# OSPLC2_2_CPU2.net
KiCad netlist of a schematic drawn in Altium Designer
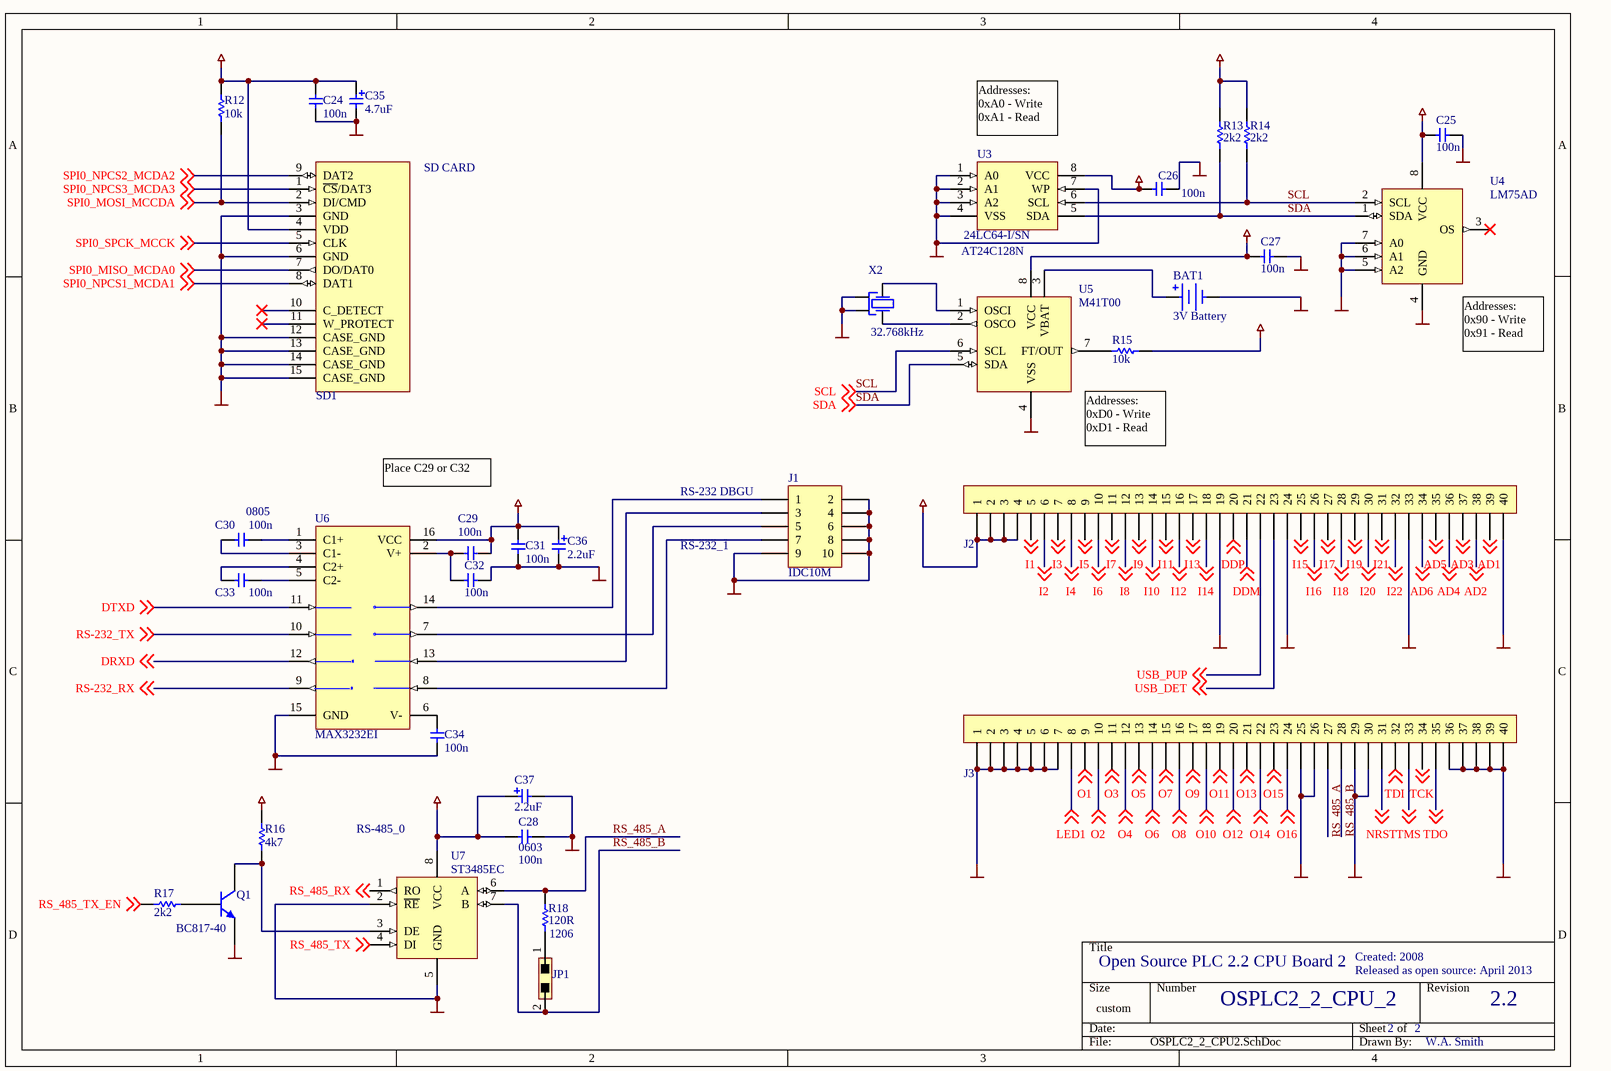
[diagram p0: OSPLC2_2_CPU2.SchDoc]

(export (version "E")
  (design (tool "Eeschema 10.0.6"))
  (components
    (comp (ref "BAT1")
      (value "3V Battery")
      (footprint "BATTERY_22MM")
      (description "3 Volt Lithium Button Battery")
      (libsource (lib "ARM_projects") (part "BATTERY_22MM"))
    )
    (comp (ref "C24")
      (value "0603")
      (footprint "0603")
      (description "0603 footprint non-polorised capacitor")
      (fields (field (name "ALTIUM_VALUE") "100n"))
      (libsource (lib "Integrated Comp_lib") (part "CAP_0603"))
    )
    (comp (ref "C25")
      (value "0603")
      (footprint "0603")
      (description "0603 footprint non-polorised capacitor")
      (fields (field (name "ALTIUM_VALUE") "100n"))
      (libsource (lib "Integrated Comp_lib") (part "CAP_0603"))
    )
    (comp (ref "C26")
      (value "0603")
      (footprint "0603")
      (description "0603 footprint non-polorised capacitor")
      (fields (field (name "ALTIUM_VALUE") "100n"))
      (libsource (lib "Integrated Comp_lib") (part "CAP_0603"))
    )
    (comp (ref "C27")
      (value "0603")
      (footprint "0603")
      (description "0603 footprint non-polorised capacitor")
      (fields (field (name "ALTIUM_VALUE") "100n"))
      (libsource (lib "Integrated Comp_lib") (part "CAP_0603"))
    )
    (comp (ref "C28")
      (value "0603")
      (footprint "0603")
      (description "0603 footprint non-polorised capacitor")
      (fields (field (name "ALTIUM_VALUE") "100n"))
      (libsource (lib "Integrated Comp_lib") (part "CAP_0603"))
    )
    (comp (ref "C29")
      (value "0805")
      (footprint "0805")
      (description "0805 footprint non-polarised capacitor")
      (fields (field (name "ALTIUM_VALUE") "100n"))
      (libsource (lib "Integrated Comp_lib") (part "CAP_0805"))
    )
    (comp (ref "C30")
      (value "0805")
      (footprint "0805")
      (description "0805 footprint non-polarised capacitor")
      (fields (field (name "ALTIUM_VALUE") "100n"))
      (libsource (lib "Integrated Comp_lib") (part "CAP_0805"))
    )
    (comp (ref "C31")
      (value "0805")
      (footprint "0805")
      (description "0805 footprint non-polarised capacitor")
      (fields (field (name "ALTIUM_VALUE") "100n"))
      (libsource (lib "Integrated Comp_lib") (part "CAP_0805"))
    )
    (comp (ref "C32")
      (value "0805")
      (footprint "0805")
      (description "0805 footprint non-polarised capacitor")
      (fields (field (name "ALTIUM_VALUE") "100n"))
      (libsource (lib "Integrated Comp_lib") (part "CAP_0805"))
    )
    (comp (ref "C33")
      (value "0805")
      (footprint "0805")
      (description "0805 footprint non-polarised capacitor")
      (fields (field (name "ALTIUM_VALUE") "100n"))
      (libsource (lib "Integrated Comp_lib") (part "CAP_0805"))
    )
    (comp (ref "C34")
      (value "0805")
      (footprint "0805")
      (description "0805 footprint non-polarised capacitor")
      (fields (field (name "ALTIUM_VALUE") "100n"))
      (libsource (lib "Integrated Comp_lib") (part "CAP_0805"))
    )
    (comp (ref "C35")
      (value "Tant_A")
      (footprint "CAP_TANT_A")
      (description "Tantalum Capacitor, A Package")
      (fields (field (name "ALTIUM_VALUE") "4.7uF"))
      (libsource (lib "Integrated Comp_lib") (part "CAP_TANT_A"))
    )
    (comp (ref "C36")
      (value "Tant_A")
      (footprint "CAP_TANT_A")
      (description "Tantalum Capacitor, A Package")
      (fields (field (name "ALTIUM_VALUE") "2.2uF"))
      (libsource (lib "Integrated Comp_lib") (part "CAP_TANT_A"))
    )
    (comp (ref "C37")
      (value "Tant_A")
      (footprint "CAP_TANT_A")
      (description "Tantalum Capacitor, A Package")
      (fields (field (name "ALTIUM_VALUE") "2.2uF"))
      (libsource (lib "Integrated Comp_lib") (part "CAP_TANT_A"))
    )
    (comp (ref "J1")
      (value "IDC10M")
      (footprint "IDC_10M_BOX")
      (description "10 pin IDC male connector, vertical, box")
      (libsource (lib "Integrated Comp_lib") (part "IDC_10M"))
    )
    (comp (ref "J2")
      (value "HEADER 1 x 40")
      (footprint "HEADER_1_40")
      (description "2.54mm header, 1 by 40")
      (libsource (lib "ARM_projects") (part "HEADER_1_40"))
    )
    (comp (ref "J3")
      (value "HEADER 1 x 40")
      (footprint "HEADER_1_40")
      (description "2.54mm header, 1 by 40")
      (libsource (lib "ARM_projects") (part "HEADER_1_40"))
    )
    (comp (ref "JP1")
      (value "JUMPER2")
      (footprint "JUMPER2_254")
      (description "2 Pin Jumper, 2.54mm")
      (libsource (lib "ARM_projects") (part "JUMPER2"))
    )
    (comp (ref "Q1")
      (value "BC817-40")
      (footprint "SO-G3/Y1")
      (description "NPN General Purpose Amplifier")
      (fields
        (field (name "MANUFACTURER") "Fairchild Semiconductor")
        (field (name "PUBLISHER") "Altium Limited")
      )
      (libsource (lib "FSC Discrete BJT") (part "BC817-40"))
    )
    (comp (ref "R12")
      (value "0805")
      (footprint "0805")
      (description "0805 footprint resistor")
      (fields (field (name "ALTIUM_VALUE") "10k"))
      (libsource (lib "Integrated Comp_lib") (part "RES_0805"))
    )
    (comp (ref "R13")
      (value "0805")
      (footprint "0805")
      (description "0805 footprint resistor")
      (fields (field (name "ALTIUM_VALUE") "2k2"))
      (libsource (lib "Integrated Comp_lib") (part "RES_0805"))
    )
    (comp (ref "R14")
      (value "0805")
      (footprint "0805")
      (description "0805 footprint resistor")
      (fields (field (name "ALTIUM_VALUE") "2k2"))
      (libsource (lib "Integrated Comp_lib") (part "RES_0805"))
    )
    (comp (ref "R15")
      (value "0805")
      (footprint "0805")
      (description "0805 footprint resistor")
      (fields (field (name "ALTIUM_VALUE") "10k"))
      (libsource (lib "Integrated Comp_lib") (part "RES_0805"))
    )
    (comp (ref "R16")
      (value "0805")
      (footprint "0805")
      (description "0805 footprint resistor")
      (fields (field (name "ALTIUM_VALUE") "4k7"))
      (libsource (lib "Integrated Comp_lib") (part "RES_0805"))
    )
    (comp (ref "R17")
      (value "0805")
      (footprint "0805")
      (description "0805 footprint resistor")
      (fields (field (name "ALTIUM_VALUE") "2k2"))
      (libsource (lib "Integrated Comp_lib") (part "RES_0805"))
    )
    (comp (ref "R18")
      (value "1206")
      (footprint "1206")
      (description "1206 footprint resistor")
      (fields (field (name "ALTIUM_VALUE") "120R"))
      (libsource (lib "Integrated Comp_lib") (part "RES_1206"))
    )
    (comp (ref "SD1")
      (value "SD Card Connector")
      (footprint "SD_CARD_GS09003P")
      (description "Secure Digital Card Connector, Amphenol, GSD09003P")
      (libsource (lib "ARM_projects") (part "SD_CARD_GSD09003P"))
    )
    (comp (ref "U3")
      (value "24LC64-I/SN")
      (footprint "SO-G8/Z7.4")
      (description "Microchip 64k bit I2C bus serial EEPROM")
      (fields (field (name "ALTIUM_VALUE") "AT24C128N"))
      (libsource (lib "Integrated Comp_lib") (part "24LC64-I/SN"))
    )
    (comp (ref "U4")
      (value "LM75AD")
      (footprint "SO-G8/X.6")
      (description "Phillips Digital temperature sensor and thermal Watchdog")
      (libsource (lib "Integrated Comp_lib") (part "LM75AD"))
    )
    (comp (ref "U5")
      (value "M41T00")
      (footprint "SO-G8/X.6")
      (description "ST Serial Access Timekeeper")
      (libsource (lib "Integrated Comp_lib") (part "M41T00"))
    )
    (comp (ref "U6")
      (value "MAX3232EI")
      (footprint "SO-G16")
      (description "3.0V TO 5.5V, Low-Power, up to 1Mbps, True RS-232 Transceiver Using Four 0.1µF External Capacitor")
      (fields (field (name "MANUFACTURER") "Maxim") (field (name "PUBLISHER") "Altium Limited"))
      (libsource (lib "Maxim Communication Transceiver") (part "MAX3232ESE"))
    )
    (comp (ref "U7")
      (value "ST3485EC")
      (footprint "SO-G8/Z7.4")
      (description "ST 3.3v RS-485/RS-422 Transceiver")
      (libsource (lib "Integrated Comp_lib") (part "ST3485EC"))
    )
    (comp (ref "X2")
      (value "32.768kHz")
      (footprint "SCM200S_SMT")
      (description "SMT 32.768kHz Crystal")
      (libsource (lib "ARM_projects") (part "SCM200S"))
    )
  )
  (nets
    (net (code "1") (name "/RS_485_A") (class "Default")
      (node (ref "J3") (pin "27") (pinfunction "27_27") (pintype "passive"))
      (node (ref "R18") (pin "2") (pinfunction "2_2") (pintype "passive"))
      (node (ref "U7") (pin "6") (pinfunction "A_6") (pintype "bidirectional"))
    )
    (net (code "2") (name "/RS_485_B") (class "Default")
      (node (ref "J3") (pin "28") (pinfunction "28_28") (pintype "passive"))
      (node (ref "JP1") (pin "2") (pinfunction "2_2") (pintype "passive"))
      (node (ref "U7") (pin "7") (pinfunction "B_7") (pintype "bidirectional"))
    )
    (net (code "3") (name "AD1") (class "Default")
      (node (ref "J2") (pin "39") (pinfunction "39_39") (pintype "passive"))
    )
    (net (code "4") (name "AD2") (class "Default")
      (node (ref "J2") (pin "38") (pinfunction "38_38") (pintype "passive"))
    )
    (net (code "5") (name "AD3") (class "Default")
      (node (ref "J2") (pin "37") (pinfunction "37_37") (pintype "passive"))
    )
    (net (code "6") (name "AD4") (class "Default")
      (node (ref "J2") (pin "36") (pinfunction "36_36") (pintype "passive"))
    )
    (net (code "7") (name "AD5") (class "Default")
      (node (ref "J2") (pin "35") (pinfunction "35_35") (pintype "passive"))
    )
    (net (code "8") (name "AD6") (class "Default")
      (node (ref "J2") (pin "34") (pinfunction "34_34") (pintype "passive"))
    )
    (net (code "9") (name "DDM") (class "Default")
      (node (ref "J2") (pin "21") (pinfunction "21_21") (pintype "passive"))
    )
    (net (code "10") (name "DDP") (class "Default")
      (node (ref "J2") (pin "20") (pinfunction "20_20") (pintype "passive"))
    )
    (net (code "11") (name "DRXD") (class "Default")
      (node (ref "U6") (pin "12") (pinfunction "R1OUT_12") (pintype "output"))
    )
    (net (code "12") (name "DTXD") (class "Default")
      (node (ref "U6") (pin "11") (pinfunction "T1IN_11") (pintype "input"))
    )
    (net (code "13") (name "GND") (class "Default")
      (node (ref "BAT1") (pin "2") (pinfunction "NEG_2") (pintype "power_in"))
      (node (ref "C24") (pin "1") (pinfunction "1_1") (pintype "passive"))
      (node (ref "C25") (pin "2") (pinfunction "2_2") (pintype "passive"))
      (node (ref "C26") (pin "2") (pinfunction "2_2") (pintype "passive"))
      (node (ref "C27") (pin "2") (pinfunction "2_2") (pintype "passive"))
      (node (ref "C28") (pin "2") (pinfunction "2_2") (pintype "passive"))
      (node (ref "C31") (pin "2") (pinfunction "2_2") (pintype "passive"))
      (node (ref "C32") (pin "1") (pinfunction "1_1") (pintype "passive"))
      (node (ref "C34") (pin "1") (pinfunction "1_1") (pintype "passive"))
      (node (ref "C35") (pin "2") (pinfunction "2_2") (pintype "passive"))
      (node (ref "C36") (pin "2") (pinfunction "2_2") (pintype "passive"))
      (node (ref "C37") (pin "2") (pinfunction "2_2") (pintype "passive"))
      (node (ref "J1") (pin "10") (pinfunction "10_10") (pintype "passive"))
      (node (ref "J1") (pin "2") (pinfunction "2_2") (pintype "passive"))
      (node (ref "J1") (pin "4") (pinfunction "4_4") (pintype "passive"))
      (node (ref "J1") (pin "6") (pinfunction "6_6") (pintype "passive"))
      (node (ref "J1") (pin "8") (pinfunction "8_8") (pintype "passive"))
      (node (ref "J1") (pin "9") (pinfunction "9_9") (pintype "passive"))
      (node (ref "J2") (pin "19") (pinfunction "19_19") (pintype "passive"))
      (node (ref "J2") (pin "24") (pinfunction "24_24") (pintype "passive"))
      (node (ref "J2") (pin "33") (pinfunction "33_33") (pintype "passive"))
      (node (ref "J2") (pin "40") (pinfunction "40_40") (pintype "passive"))
      (node (ref "J3") (pin "1") (pinfunction "1_1") (pintype "passive"))
      (node (ref "J3") (pin "2") (pinfunction "2_2") (pintype "passive"))
      (node (ref "J3") (pin "25") (pinfunction "25_25") (pintype "passive"))
      (node (ref "J3") (pin "26") (pinfunction "26_26") (pintype "passive"))
      (node (ref "J3") (pin "29") (pinfunction "29_29") (pintype "passive"))
      (node (ref "J3") (pin "3") (pinfunction "3_3") (pintype "passive"))
      (node (ref "J3") (pin "30") (pinfunction "30_30") (pintype "passive"))
      (node (ref "J3") (pin "36") (pinfunction "36_36") (pintype "passive"))
      (node (ref "J3") (pin "37") (pinfunction "37_37") (pintype "passive"))
      (node (ref "J3") (pin "38") (pinfunction "38_38") (pintype "passive"))
      (node (ref "J3") (pin "39") (pinfunction "39_39") (pintype "passive"))
      (node (ref "J3") (pin "4") (pinfunction "4_4") (pintype "passive"))
      (node (ref "J3") (pin "40") (pinfunction "40_40") (pintype "passive"))
      (node (ref "J3") (pin "5") (pinfunction "5_5") (pintype "passive"))
      (node (ref "J3") (pin "6") (pinfunction "6_6") (pintype "passive"))
      (node (ref "J3") (pin "7") (pinfunction "7_7") (pintype "passive"))
      (node (ref "Q1") (pin "2") (pinfunction "E_2") (pintype "passive"))
      (node (ref "SD1") (pin "12") (pinfunction "CASE_GND_12") (pintype "power_in"))
      (node (ref "SD1") (pin "13") (pinfunction "CASE_GND_13") (pintype "power_in"))
      (node (ref "SD1") (pin "14") (pinfunction "CASE_GND_14") (pintype "power_in"))
      (node (ref "SD1") (pin "15") (pinfunction "CASE_GND_15") (pintype "power_in"))
      (node (ref "SD1") (pin "3") (pinfunction "GND_3") (pintype "power_in"))
      (node (ref "SD1") (pin "6") (pinfunction "GND_6") (pintype "power_in"))
      (node (ref "U3") (pin "1") (pinfunction "A0_1") (pintype "input"))
      (node (ref "U3") (pin "2") (pinfunction "A1_2") (pintype "input"))
      (node (ref "U3") (pin "3") (pinfunction "A2_3") (pintype "input"))
      (node (ref "U3") (pin "4") (pinfunction "VSS_4") (pintype "power_in"))
      (node (ref "U3") (pin "7") (pinfunction "WP_7") (pintype "input"))
      (node (ref "U4") (pin "4") (pinfunction "GND_4") (pintype "power_in"))
      (node (ref "U4") (pin "5") (pinfunction "A2_5") (pintype "input"))
      (node (ref "U4") (pin "6") (pinfunction "A1_6") (pintype "input"))
      (node (ref "U4") (pin "7") (pinfunction "A0_7") (pintype "input"))
      (node (ref "U5") (pin "4") (pinfunction "VSS_4") (pintype "power_in"))
      (node (ref "U6") (pin "15") (pinfunction "GND_15") (pintype "power_in"))
      (node (ref "U7") (pin "2") (pinfunction "~{RE}_2") (pintype "input"))
      (node (ref "U7") (pin "5") (pinfunction "GND_5") (pintype "power_in"))
      (node (ref "X2") (pin "2") (pinfunction "GND_2") (pintype "power_in"))
      (node (ref "X2") (pin "3") (pinfunction "GND_3") (pintype "power_in"))
    )
    (net (code "14") (name "I1") (class "Default")
      (node (ref "J2") (pin "5") (pinfunction "5_5") (pintype "passive"))
    )
    (net (code "15") (name "I2") (class "Default")
      (node (ref "J2") (pin "6") (pinfunction "6_6") (pintype "passive"))
    )
    (net (code "16") (name "I3") (class "Default")
      (node (ref "J2") (pin "7") (pinfunction "7_7") (pintype "passive"))
    )
    (net (code "17") (name "I4") (class "Default")
      (node (ref "J2") (pin "8") (pinfunction "8_8") (pintype "passive"))
    )
    (net (code "18") (name "I5") (class "Default")
      (node (ref "J2") (pin "9") (pinfunction "9_9") (pintype "passive"))
    )
    (net (code "19") (name "I6") (class "Default")
      (node (ref "J2") (pin "10") (pinfunction "10_10") (pintype "passive"))
    )
    (net (code "20") (name "I7") (class "Default")
      (node (ref "J2") (pin "11") (pinfunction "11_11") (pintype "passive"))
    )
    (net (code "21") (name "I8") (class "Default")
      (node (ref "J2") (pin "12") (pinfunction "12_12") (pintype "passive"))
    )
    (net (code "22") (name "I9") (class "Default")
      (node (ref "J2") (pin "13") (pinfunction "13_13") (pintype "passive"))
    )
    (net (code "23") (name "I10") (class "Default")
      (node (ref "J2") (pin "14") (pinfunction "14_14") (pintype "passive"))
    )
    (net (code "24") (name "I11") (class "Default")
      (node (ref "J2") (pin "15") (pinfunction "15_15") (pintype "passive"))
    )
    (net (code "25") (name "I12") (class "Default")
      (node (ref "J2") (pin "16") (pinfunction "16_16") (pintype "passive"))
    )
    (net (code "26") (name "I13") (class "Default")
      (node (ref "J2") (pin "17") (pinfunction "17_17") (pintype "passive"))
    )
    (net (code "27") (name "I14") (class "Default")
      (node (ref "J2") (pin "18") (pinfunction "18_18") (pintype "passive"))
    )
    (net (code "28") (name "I15") (class "Default")
      (node (ref "J2") (pin "25") (pinfunction "25_25") (pintype "passive"))
    )
    (net (code "29") (name "I16") (class "Default")
      (node (ref "J2") (pin "26") (pinfunction "26_26") (pintype "passive"))
    )
    (net (code "30") (name "I17") (class "Default")
      (node (ref "J2") (pin "27") (pinfunction "27_27") (pintype "passive"))
    )
    (net (code "31") (name "I18") (class "Default")
      (node (ref "J2") (pin "28") (pinfunction "28_28") (pintype "passive"))
    )
    (net (code "32") (name "I19") (class "Default")
      (node (ref "J2") (pin "29") (pinfunction "29_29") (pintype "passive"))
    )
    (net (code "33") (name "I20") (class "Default")
      (node (ref "J2") (pin "30") (pinfunction "30_30") (pintype "passive"))
    )
    (net (code "34") (name "I21") (class "Default")
      (node (ref "J2") (pin "31") (pinfunction "31_31") (pintype "passive"))
    )
    (net (code "35") (name "I22") (class "Default")
      (node (ref "J2") (pin "32") (pinfunction "32_32") (pintype "passive"))
    )
    (net (code "36") (name "LED1") (class "Default")
      (node (ref "J3") (pin "8") (pinfunction "8_8") (pintype "passive"))
    )
    (net (code "37") (name "NRST") (class "Default")
      (node (ref "J3") (pin "31") (pinfunction "31_31") (pintype "passive"))
    )
    (net (code "38") (name "Net-(BAT1-POS)") (class "Default")
      (node (ref "BAT1") (pin "1") (pinfunction "POS_1") (pintype "power_in"))
      (node (ref "U5") (pin "3") (pinfunction "VBAT_3") (pintype "power_in"))
    )
    (net (code "39") (name "Net-(JP1-Pad1)") (class "Default")
      (node (ref "JP1") (pin "1") (pinfunction "1_1") (pintype "passive"))
      (node (ref "R18") (pin "1") (pinfunction "1_1") (pintype "passive"))
    )
    (net (code "40") (name "Net-(Q1-B)") (class "Default")
      (node (ref "Q1") (pin "1") (pinfunction "B_1") (pintype "passive"))
      (node (ref "R17") (pin "1") (pinfunction "1_1") (pintype "passive"))
    )
    (net (code "41") (name "Net-(Q1-C)") (class "Default")
      (node (ref "Q1") (pin "3") (pinfunction "C_3") (pintype "passive"))
      (node (ref "R16") (pin "1") (pinfunction "1_1") (pintype "passive"))
      (node (ref "U7") (pin "3") (pinfunction "DE_3") (pintype "input"))
    )
    (net (code "42") (name "Net-(U5-FT{slash}OUT)") (class "Default")
      (node (ref "R15") (pin "1") (pinfunction "1_1") (pintype "passive"))
      (node (ref "U5") (pin "7") (pinfunction "FT/OUT_7") (pintype "output"))
    )
    (net (code "43") (name "Net-(U5-OSCI)") (class "Default")
      (node (ref "U5") (pin "1") (pinfunction "OSCI_1") (pintype "input"))
      (node (ref "X2") (pin "1") (pinfunction "X_1") (pintype "passive"))
    )
    (net (code "44") (name "Net-(U5-OSCO)") (class "Default")
      (node (ref "U5") (pin "2") (pinfunction "OSCO_2") (pintype "output"))
      (node (ref "X2") (pin "4") (pinfunction "X_4") (pintype "passive"))
    )
    (net (code "45") (name "Net-(U6-C1+)") (class "Default")
      (node (ref "C30") (pin "1") (pinfunction "1_1") (pintype "passive"))
      (node (ref "U6") (pin "1") (pinfunction "C1+_1") (pintype "passive"))
    )
    (net (code "46") (name "Net-(U6-C1-)") (class "Default")
      (node (ref "C30") (pin "2") (pinfunction "2_2") (pintype "passive"))
      (node (ref "U6") (pin "3") (pinfunction "C1-_3") (pintype "passive"))
    )
    (net (code "47") (name "Net-(U6-C2+)") (class "Default")
      (node (ref "C33") (pin "2") (pinfunction "2_2") (pintype "passive"))
      (node (ref "U6") (pin "4") (pinfunction "C2+_4") (pintype "passive"))
    )
    (net (code "48") (name "Net-(U6-C2-)") (class "Default")
      (node (ref "C33") (pin "1") (pinfunction "1_1") (pintype "passive"))
      (node (ref "U6") (pin "5") (pinfunction "C2-_5") (pintype "passive"))
    )
    (net (code "49") (name "Net-(U6-R1IN)") (class "Default")
      (node (ref "J1") (pin "3") (pinfunction "3_3") (pintype "passive"))
      (node (ref "U6") (pin "13") (pinfunction "R1IN_13") (pintype "input"))
    )
    (net (code "50") (name "Net-(U6-R2IN)") (class "Default")
      (node (ref "J1") (pin "7") (pinfunction "7_7") (pintype "passive"))
      (node (ref "U6") (pin "8") (pinfunction "R2IN_8") (pintype "input"))
    )
    (net (code "51") (name "Net-(U6-T1OUT)") (class "Default")
      (node (ref "J1") (pin "1") (pinfunction "1_1") (pintype "passive"))
      (node (ref "U6") (pin "14") (pinfunction "T1OUT_14") (pintype "output"))
    )
    (net (code "52") (name "Net-(U6-T2OUT)") (class "Default")
      (node (ref "J1") (pin "5") (pinfunction "5_5") (pintype "passive"))
      (node (ref "U6") (pin "7") (pinfunction "T2OUT_7") (pintype "output"))
    )
    (net (code "53") (name "Net-(U6-V+)") (class "Default")
      (node (ref "C29") (pin "2") (pinfunction "2_2") (pintype "passive"))
      (node (ref "C32") (pin "2") (pinfunction "2_2") (pintype "passive"))
      (node (ref "U6") (pin "2") (pinfunction "V+_2") (pintype "power_in"))
    )
    (net (code "54") (name "Net-(U6-V-)") (class "Default")
      (node (ref "C34") (pin "2") (pinfunction "2_2") (pintype "passive"))
      (node (ref "U6") (pin "6") (pinfunction "V-_6") (pintype "power_in"))
    )
    (net (code "55") (name "O1") (class "Default")
      (node (ref "J3") (pin "9") (pinfunction "9_9") (pintype "passive"))
    )
    (net (code "56") (name "O2") (class "Default")
      (node (ref "J3") (pin "10") (pinfunction "10_10") (pintype "passive"))
    )
    (net (code "57") (name "O3") (class "Default")
      (node (ref "J3") (pin "11") (pinfunction "11_11") (pintype "passive"))
    )
    (net (code "58") (name "O4") (class "Default")
      (node (ref "J3") (pin "12") (pinfunction "12_12") (pintype "passive"))
    )
    (net (code "59") (name "O5") (class "Default")
      (node (ref "J3") (pin "13") (pinfunction "13_13") (pintype "passive"))
    )
    (net (code "60") (name "O6") (class "Default")
      (node (ref "J3") (pin "14") (pinfunction "14_14") (pintype "passive"))
    )
    (net (code "61") (name "O7") (class "Default")
      (node (ref "J3") (pin "15") (pinfunction "15_15") (pintype "passive"))
    )
    (net (code "62") (name "O8") (class "Default")
      (node (ref "J3") (pin "16") (pinfunction "16_16") (pintype "passive"))
    )
    (net (code "63") (name "O9") (class "Default")
      (node (ref "J3") (pin "17") (pinfunction "17_17") (pintype "passive"))
    )
    (net (code "64") (name "O10") (class "Default")
      (node (ref "J3") (pin "18") (pinfunction "18_18") (pintype "passive"))
    )
    (net (code "65") (name "O11") (class "Default")
      (node (ref "J3") (pin "19") (pinfunction "19_19") (pintype "passive"))
    )
    (net (code "66") (name "O12") (class "Default")
      (node (ref "J3") (pin "20") (pinfunction "20_20") (pintype "passive"))
    )
    (net (code "67") (name "O13") (class "Default")
      (node (ref "J3") (pin "21") (pinfunction "21_21") (pintype "passive"))
    )
    (net (code "68") (name "O14") (class "Default")
      (node (ref "J3") (pin "22") (pinfunction "22_22") (pintype "passive"))
    )
    (net (code "69") (name "O15") (class "Default")
      (node (ref "J3") (pin "23") (pinfunction "23_23") (pintype "passive"))
    )
    (net (code "70") (name "O16") (class "Default")
      (node (ref "J3") (pin "24") (pinfunction "24_24") (pintype "passive"))
    )
    (net (code "71") (name "RS-232_RX") (class "Default")
      (node (ref "U6") (pin "9") (pinfunction "R2OUT_9") (pintype "output"))
    )
    (net (code "72") (name "RS-232_TX") (class "Default")
      (node (ref "U6") (pin "10") (pinfunction "T2IN_10") (pintype "input"))
    )
    (net (code "73") (name "RS_485_RX") (class "Default")
      (node (ref "U7") (pin "1") (pinfunction "RO_1") (pintype "output"))
    )
    (net (code "74") (name "RS_485_TX") (class "Default")
      (node (ref "U7") (pin "4") (pinfunction "DI_4") (pintype "input"))
    )
    (net (code "75") (name "RS_485_TX_EN") (class "Default")
      (node (ref "R17") (pin "2") (pinfunction "2_2") (pintype "passive"))
    )
    (net (code "76") (name "SCL") (class "Default")
      (node (ref "R14") (pin "1") (pinfunction "1_1") (pintype "passive"))
      (node (ref "U3") (pin "6") (pinfunction "SCL_6") (pintype "input"))
      (node (ref "U4") (pin "2") (pinfunction "SCL_2") (pintype "input"))
      (node (ref "U5") (pin "6") (pinfunction "SCL_6") (pintype "input"))
    )
    (net (code "77") (name "SDA") (class "Default")
      (node (ref "R13") (pin "1") (pinfunction "1_1") (pintype "passive"))
      (node (ref "U3") (pin "5") (pinfunction "SDA_5") (pintype "open_collector"))
      (node (ref "U4") (pin "1") (pinfunction "SDA_1") (pintype "bidirectional"))
      (node (ref "U5") (pin "5") (pinfunction "SDA_5") (pintype "bidirectional"))
    )
    (net (code "78") (name "SPI0_MISO_MCDA0") (class "Default")
      (node (ref "SD1") (pin "7") (pinfunction "DO/DAT0_7") (pintype "output"))
    )
    (net (code "79") (name "SPI0_MOSI_MCCDA") (class "Default")
      (node (ref "R12") (pin "1") (pinfunction "1_1") (pintype "passive"))
      (node (ref "SD1") (pin "2") (pinfunction "DI/CMD_2") (pintype "input"))
    )
    (net (code "80") (name "SPI0_NPCS1_MCDA1") (class "Default")
      (node (ref "SD1") (pin "8") (pinfunction "DAT1_8") (pintype "bidirectional"))
    )
    (net (code "81") (name "SPI0_NPCS2_MCDA2") (class "Default")
      (node (ref "SD1") (pin "9") (pinfunction "DAT2_9") (pintype "bidirectional"))
    )
    (net (code "82") (name "SPI0_NPCS3_MCDA3") (class "Default")
      (node (ref "SD1") (pin "1") (pinfunction "~{CS}/DAT3_1") (pintype "input"))
    )
    (net (code "83") (name "SPI0_SPCK_MCCK") (class "Default")
      (node (ref "SD1") (pin "5") (pinfunction "CLK_5") (pintype "input"))
    )
    (net (code "84") (name "TCK") (class "Default")
      (node (ref "J3") (pin "34") (pinfunction "34_34") (pintype "passive"))
    )
    (net (code "85") (name "TDI") (class "Default")
      (node (ref "J3") (pin "32") (pinfunction "32_32") (pintype "passive"))
    )
    (net (code "86") (name "TDO") (class "Default")
      (node (ref "J3") (pin "35") (pinfunction "35_35") (pintype "passive"))
    )
    (net (code "87") (name "TMS") (class "Default")
      (node (ref "J3") (pin "33") (pinfunction "33_33") (pintype "passive"))
    )
    (net (code "88") (name "USB_DET") (class "Default")
      (node (ref "J2") (pin "23") (pinfunction "23_23") (pintype "passive"))
    )
    (net (code "89") (name "USB_PUP") (class "Default")
      (node (ref "J2") (pin "22") (pinfunction "22_22") (pintype "passive"))
    )
    (net (code "90") (name "VCC3v3") (class "Default")
      (node (ref "C24") (pin "2") (pinfunction "2_2") (pintype "passive"))
      (node (ref "C25") (pin "1") (pinfunction "1_1") (pintype "passive"))
      (node (ref "C26") (pin "1") (pinfunction "1_1") (pintype "passive"))
      (node (ref "C27") (pin "1") (pinfunction "1_1") (pintype "passive"))
      (node (ref "C28") (pin "1") (pinfunction "1_1") (pintype "passive"))
      (node (ref "C29") (pin "1") (pinfunction "1_1") (pintype "passive"))
      (node (ref "C31") (pin "1") (pinfunction "1_1") (pintype "passive"))
      (node (ref "C35") (pin "1") (pinfunction "1_1") (pintype "passive"))
      (node (ref "C36") (pin "1") (pinfunction "1_1") (pintype "passive"))
      (node (ref "C37") (pin "1") (pinfunction "1_1") (pintype "passive"))
      (node (ref "J2") (pin "1") (pinfunction "1_1") (pintype "passive"))
      (node (ref "J2") (pin "2") (pinfunction "2_2") (pintype "passive"))
      (node (ref "J2") (pin "3") (pinfunction "3_3") (pintype "passive"))
      (node (ref "J2") (pin "4") (pinfunction "4_4") (pintype "passive"))
      (node (ref "R12") (pin "2") (pinfunction "2_2") (pintype "passive"))
      (node (ref "R13") (pin "2") (pinfunction "2_2") (pintype "passive"))
      (node (ref "R14") (pin "2") (pinfunction "2_2") (pintype "passive"))
      (node (ref "R15") (pin "2") (pinfunction "2_2") (pintype "passive"))
      (node (ref "R16") (pin "2") (pinfunction "2_2") (pintype "passive"))
      (node (ref "SD1") (pin "4") (pinfunction "VDD_4") (pintype "power_in"))
      (node (ref "U3") (pin "8") (pinfunction "VCC_8") (pintype "power_in"))
      (node (ref "U4") (pin "8") (pinfunction "VCC_8") (pintype "power_in"))
      (node (ref "U5") (pin "8") (pinfunction "VCC_8") (pintype "power_in"))
      (node (ref "U6") (pin "16") (pinfunction "VCC_16") (pintype "power_in"))
      (node (ref "U7") (pin "8") (pinfunction "VCC_8") (pintype "power_in"))
    )
    (net (code "91") (name "unconnected-(SD1-C_DETECT-Pad10)") (class "Default")
      (node (ref "SD1") (pin "10") (pinfunction "C_DETECT_10") (pintype "passive+no_connect"))
    )
    (net (code "92") (name "unconnected-(SD1-W_PROTECT-Pad11)") (class "Default")
      (node (ref "SD1") (pin "11") (pinfunction "W_PROTECT_11") (pintype "passive+no_connect"))
    )
    (net (code "93") (name "unconnected-(U4-OS-Pad3)") (class "Default")
      (node (ref "U4") (pin "3") (pinfunction "OS_3") (pintype "output+no_connect"))
    )
  )
)
